# -.net
KiCad netlist of a schematic drawn in EasyEDA Pro
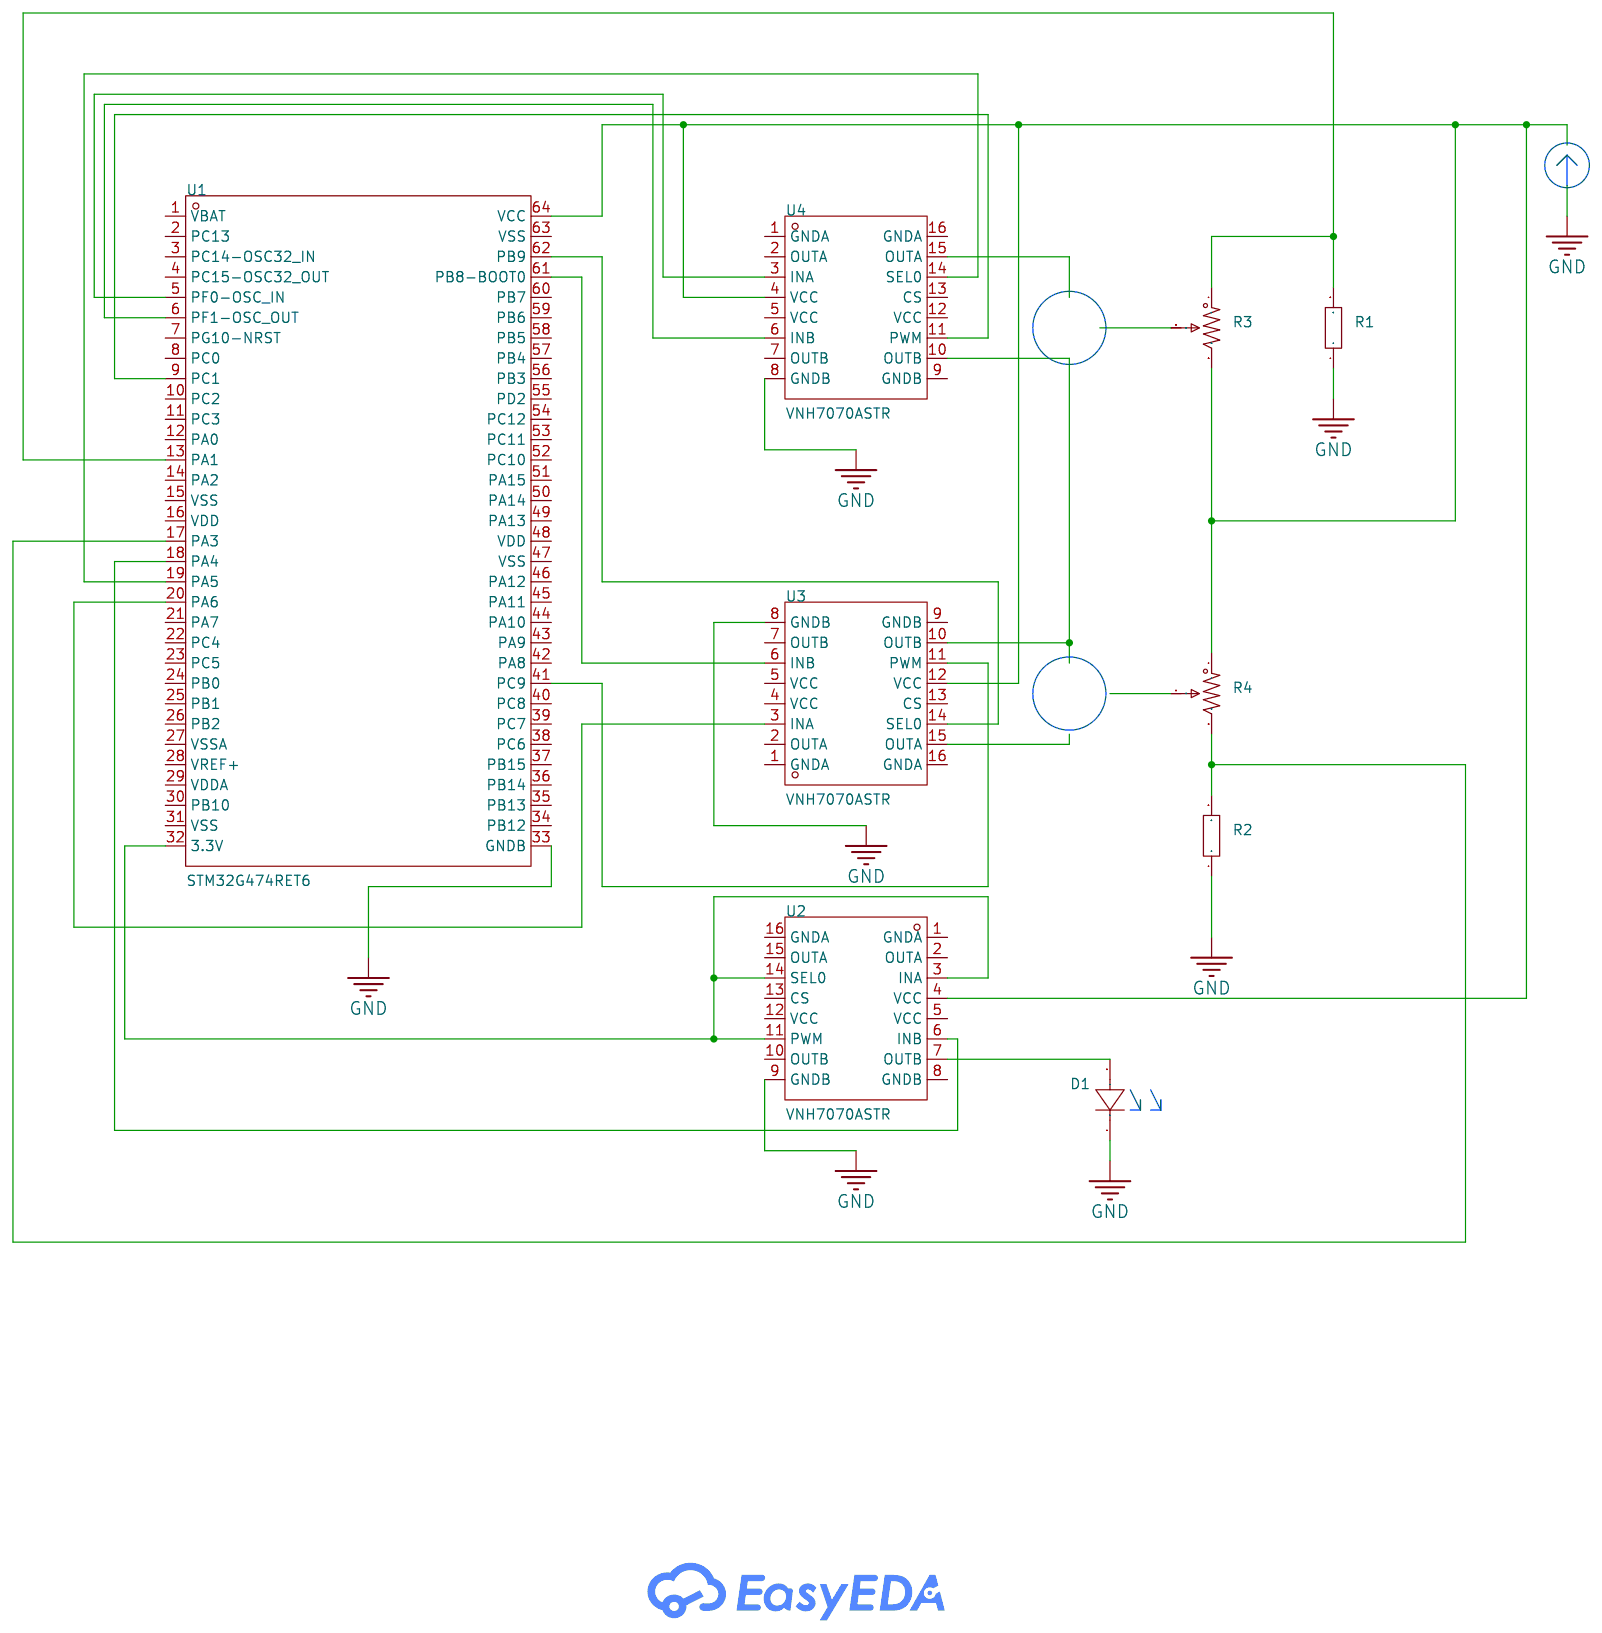
[diagram p0: schematic sheet]

(export (version "E")
  (design (tool "Eeschema 10.0.6"))
  (components
    (comp (ref "D1")
      (value "~")
      (footprint "easyedapro:SMA_L4.4-W2.8-LS5.4-RD")
      (libsource (lib "easyedapro") (part "D_1N4007"))
    )
    (comp (ref "R1")
      (value "10mΩ")
      (footprint "easyedapro:R1206")
      (fields (field (name "Manufacturer Part") "FMF06FTHR010-LH") (field (name "Manufacturer") "PSA(信昌电陶)"))
      (libsource (lib "easyedapro") (part "FMF06FTHR010-LHL"))
    )
    (comp (ref "R2")
      (value "10mΩ")
      (footprint "easyedapro:R1206")
      (fields (field (name "Manufacturer Part") "FMF06FTHR010-LH") (field (name "Manufacturer") "PSA(信昌电陶)"))
      (libsource (lib "easyedapro") (part "FMF06FTHR010-LHL"))
    )
    (comp (ref "R3")
      (value "10kΩ")
      (footprint "easyedapro:RES-ADJ-TH_3362P")
      (description "Resistance: Tolerance:±10% Tolerance:±10%")
      (fields (field (name "Manufacturer Part") "3362P-1-103") (field (name "Manufacturer") "BOCHEN(博晨)"))
      (libsource (lib "easyedapro") (part "3362P-1-103_C118956"))
    )
    (comp (ref "R4")
      (value "10kΩ")
      (footprint "easyedapro:RES-ADJ-TH_3362P")
      (description "Resistance: Tolerance:±10% Tolerance:±10%")
      (fields (field (name "Manufacturer Part") "3362P-1-103") (field (name "Manufacturer") "BOCHEN(博晨)"))
      (libsource (lib "easyedapro") (part "3362P-1-103_C118956"))
    )
    (comp (ref "U1")
      (value "STM32G474RET6")
      (footprint "easyedapro:LQFP-64_L10.0-W10.0-P0.50-LS12.0-BL")
      (fields (field (name "Manufacturer") "ST(意法半导体)"))
      (libsource (lib "easyedapro") (part "STM32G474RET6"))
    )
    (comp (ref "U2")
      (value "VNH7070ASTR")
      (footprint "easyedapro:SOIC-16_L9.9-W3.9-P1.27-LS6.0-BL")
      (fields (field (name "Manufacturer") "ST(意法半导体)"))
      (libsource (lib "easyedapro") (part "VNH7070ASTR"))
    )
    (comp (ref "U3")
      (value "VNH7070ASTR")
      (footprint "easyedapro:SOIC-16_L9.9-W3.9-P1.27-LS6.0-BL")
      (fields (field (name "Manufacturer") "ST(意法半导体)"))
      (libsource (lib "easyedapro") (part "VNH7070ASTR"))
    )
    (comp (ref "U4")
      (value "VNH7070ASTR")
      (footprint "easyedapro:SOIC-16_L9.9-W3.9-P1.27-LS6.0-BL")
      (fields (field (name "Manufacturer") "ST(意法半导体)"))
      (libsource (lib "easyedapro") (part "VNH7070ASTR"))
    )
  )
  (nets
    (net (code "1") (name "GND") (class "Default")
      (node (ref "D1") (pin "1") (pinfunction "K_1") (pintype "input"))
      (node (ref "R1") (pin "1") (pinfunction "1_1") (pintype "input"))
      (node (ref "R2") (pin "1") (pinfunction "1_1") (pintype "input"))
      (node (ref "U1") (pin "33") (pinfunction "GNDB_33") (pintype "unspecified"))
      (node (ref "U2") (pin "9") (pinfunction "GNDB_9") (pintype "unspecified"))
      (node (ref "U3") (pin "8") (pinfunction "GNDB_8") (pintype "unspecified"))
      (node (ref "U4") (pin "8") (pinfunction "GNDB_8") (pintype "unspecified"))
    )
    (net (code "2") (name "Net-(D1-A)") (class "Default")
      (node (ref "D1") (pin "2") (pinfunction "A_2") (pintype "input"))
      (node (ref "U2") (pin "7") (pinfunction "OUTB_7") (pintype "unspecified"))
    )
    (net (code "3") (name "Net-(U1-3.3V)") (class "Default")
      (node (ref "U1") (pin "32") (pinfunction "3.3V_32") (pintype "unspecified"))
      (node (ref "U2") (pin "11") (pinfunction "PWM_11") (pintype "unspecified"))
      (node (ref "U2") (pin "14") (pinfunction "SEL0_14") (pintype "unspecified"))
      (node (ref "U2") (pin "3") (pinfunction "INA_3") (pintype "unspecified"))
    )
    (net (code "4") (name "Net-(U1-PA1)") (class "Default")
      (node (ref "R1") (pin "2") (pinfunction "2_2") (pintype "input"))
      (node (ref "R3") (pin "1") (pinfunction "1_1") (pintype "unspecified"))
      (node (ref "U1") (pin "13") (pinfunction "PA1_13") (pintype "unspecified"))
    )
    (net (code "5") (name "Net-(U1-PA3)") (class "Default")
      (node (ref "R2") (pin "2") (pinfunction "2_2") (pintype "input"))
      (node (ref "R4") (pin "3") (pinfunction "3_3") (pintype "unspecified"))
      (node (ref "U1") (pin "17") (pinfunction "PA3_17") (pintype "unspecified"))
    )
    (net (code "6") (name "Net-(U1-PA4)") (class "Default")
      (node (ref "U1") (pin "18") (pinfunction "PA4_18") (pintype "unspecified"))
      (node (ref "U2") (pin "6") (pinfunction "INB_6") (pintype "unspecified"))
    )
    (net (code "7") (name "Net-(U1-PA5)") (class "Default")
      (node (ref "U1") (pin "19") (pinfunction "PA5_19") (pintype "unspecified"))
      (node (ref "U4") (pin "14") (pinfunction "SEL0_14") (pintype "unspecified"))
    )
    (net (code "8") (name "Net-(U1-PA6)") (class "Default")
      (node (ref "U1") (pin "20") (pinfunction "PA6_20") (pintype "unspecified"))
      (node (ref "U3") (pin "3") (pinfunction "INA_3") (pintype "unspecified"))
    )
    (net (code "9") (name "Net-(U1-PB8-BOOT0)") (class "Default")
      (node (ref "U1") (pin "61") (pinfunction "PB8-BOOT0_61") (pintype "unspecified"))
      (node (ref "U3") (pin "6") (pinfunction "INB_6") (pintype "unspecified"))
    )
    (net (code "10") (name "Net-(U1-PB9)") (class "Default")
      (node (ref "U1") (pin "62") (pinfunction "PB9_62") (pintype "unspecified"))
      (node (ref "U3") (pin "14") (pinfunction "SEL0_14") (pintype "unspecified"))
    )
    (net (code "11") (name "Net-(U1-PC1)") (class "Default")
      (node (ref "U1") (pin "9") (pinfunction "PC1_9") (pintype "unspecified"))
      (node (ref "U4") (pin "11") (pinfunction "PWM_11") (pintype "unspecified"))
    )
    (net (code "12") (name "Net-(U1-PC9)") (class "Default")
      (node (ref "U1") (pin "41") (pinfunction "PC9_41") (pintype "unspecified"))
      (node (ref "U3") (pin "11") (pinfunction "PWM_11") (pintype "unspecified"))
    )
    (net (code "13") (name "Net-(U1-PF0-OSC_IN)") (class "Default")
      (node (ref "U1") (pin "5") (pinfunction "PF0-OSC_IN_5") (pintype "unspecified"))
      (node (ref "U4") (pin "3") (pinfunction "INA_3") (pintype "unspecified"))
    )
    (net (code "14") (name "Net-(U1-PF1-OSC_OUT)") (class "Default")
      (node (ref "U1") (pin "6") (pinfunction "PF1-OSC_OUT_6") (pintype "unspecified"))
      (node (ref "U4") (pin "6") (pinfunction "INB_6") (pintype "unspecified"))
    )
    (net (code "15") (name "Net-(U1-VCC)") (class "Default")
      (node (ref "R3") (pin "3") (pinfunction "3_3") (pintype "unspecified"))
      (node (ref "R4") (pin "1") (pinfunction "1_1") (pintype "unspecified"))
      (node (ref "U1") (pin "64") (pinfunction "VCC_64") (pintype "unspecified"))
      (node (ref "U2") (pin "4") (pinfunction "VCC_4") (pintype "unspecified"))
      (node (ref "U3") (pin "12") (pinfunction "VCC_12") (pintype "unspecified"))
      (node (ref "U4") (pin "4") (pinfunction "VCC_4") (pintype "unspecified"))
    )
    (net (code "16") (name "Net-(U3-OUTB-Pad10)") (class "Default")
      (node (ref "U3") (pin "10") (pinfunction "OUTB_10") (pintype "unspecified"))
      (node (ref "U4") (pin "10") (pinfunction "OUTB_10") (pintype "unspecified"))
    )
    (net (code "17") (name "unconnected-(R3-Pad2)") (class "Default")
      (node (ref "R3") (pin "2") (pinfunction "2_2") (pintype "unspecified"))
    )
    (net (code "18") (name "unconnected-(R4-Pad2)") (class "Default")
      (node (ref "R4") (pin "2") (pinfunction "2_2") (pintype "unspecified"))
    )
    (net (code "19") (name "unconnected-(U1-PA0-Pad12)") (class "Default")
      (node (ref "U1") (pin "12") (pinfunction "PA0_12") (pintype "unspecified"))
    )
    (net (code "20") (name "unconnected-(U1-PA2-Pad14)") (class "Default")
      (node (ref "U1") (pin "14") (pinfunction "PA2_14") (pintype "unspecified"))
    )
    (net (code "21") (name "unconnected-(U1-PA7-Pad21)") (class "Default")
      (node (ref "U1") (pin "21") (pinfunction "PA7_21") (pintype "unspecified"))
    )
    (net (code "22") (name "unconnected-(U1-PA8-Pad42)") (class "Default")
      (node (ref "U1") (pin "42") (pinfunction "PA8_42") (pintype "unspecified"))
    )
    (net (code "23") (name "unconnected-(U1-PA9-Pad43)") (class "Default")
      (node (ref "U1") (pin "43") (pinfunction "PA9_43") (pintype "unspecified"))
    )
    (net (code "24") (name "unconnected-(U1-PA10-Pad44)") (class "Default")
      (node (ref "U1") (pin "44") (pinfunction "PA10_44") (pintype "unspecified"))
    )
    (net (code "25") (name "unconnected-(U1-PA11-Pad45)") (class "Default")
      (node (ref "U1") (pin "45") (pinfunction "PA11_45") (pintype "unspecified"))
    )
    (net (code "26") (name "unconnected-(U1-PA12-Pad46)") (class "Default")
      (node (ref "U1") (pin "46") (pinfunction "PA12_46") (pintype "unspecified"))
    )
    (net (code "27") (name "unconnected-(U1-PA13-Pad49)") (class "Default")
      (node (ref "U1") (pin "49") (pinfunction "PA13_49") (pintype "unspecified"))
    )
    (net (code "28") (name "unconnected-(U1-PA14-Pad50)") (class "Default")
      (node (ref "U1") (pin "50") (pinfunction "PA14_50") (pintype "unspecified"))
    )
    (net (code "29") (name "unconnected-(U1-PA15-Pad51)") (class "Default")
      (node (ref "U1") (pin "51") (pinfunction "PA15_51") (pintype "unspecified"))
    )
    (net (code "30") (name "unconnected-(U1-PB0-Pad24)") (class "Default")
      (node (ref "U1") (pin "24") (pinfunction "PB0_24") (pintype "unspecified"))
    )
    (net (code "31") (name "unconnected-(U1-PB1-Pad25)") (class "Default")
      (node (ref "U1") (pin "25") (pinfunction "PB1_25") (pintype "unspecified"))
    )
    (net (code "32") (name "unconnected-(U1-PB2-Pad26)") (class "Default")
      (node (ref "U1") (pin "26") (pinfunction "PB2_26") (pintype "unspecified"))
    )
    (net (code "33") (name "unconnected-(U1-PB3-Pad56)") (class "Default")
      (node (ref "U1") (pin "56") (pinfunction "PB3_56") (pintype "unspecified"))
    )
    (net (code "34") (name "unconnected-(U1-PB4-Pad57)") (class "Default")
      (node (ref "U1") (pin "57") (pinfunction "PB4_57") (pintype "unspecified"))
    )
    (net (code "35") (name "unconnected-(U1-PB5-Pad58)") (class "Default")
      (node (ref "U1") (pin "58") (pinfunction "PB5_58") (pintype "unspecified"))
    )
    (net (code "36") (name "unconnected-(U1-PB6-Pad59)") (class "Default")
      (node (ref "U1") (pin "59") (pinfunction "PB6_59") (pintype "unspecified"))
    )
    (net (code "37") (name "unconnected-(U1-PB7-Pad60)") (class "Default")
      (node (ref "U1") (pin "60") (pinfunction "PB7_60") (pintype "unspecified"))
    )
    (net (code "38") (name "unconnected-(U1-PB10-Pad30)") (class "Default")
      (node (ref "U1") (pin "30") (pinfunction "PB10_30") (pintype "unspecified"))
    )
    (net (code "39") (name "unconnected-(U1-PB12-Pad34)") (class "Default")
      (node (ref "U1") (pin "34") (pinfunction "PB12_34") (pintype "unspecified"))
    )
    (net (code "40") (name "unconnected-(U1-PB13-Pad35)") (class "Default")
      (node (ref "U1") (pin "35") (pinfunction "PB13_35") (pintype "unspecified"))
    )
    (net (code "41") (name "unconnected-(U1-PB14-Pad36)") (class "Default")
      (node (ref "U1") (pin "36") (pinfunction "PB14_36") (pintype "unspecified"))
    )
    (net (code "42") (name "unconnected-(U1-PB15-Pad37)") (class "Default")
      (node (ref "U1") (pin "37") (pinfunction "PB15_37") (pintype "unspecified"))
    )
    (net (code "43") (name "unconnected-(U1-PC0-Pad8)") (class "Default")
      (node (ref "U1") (pin "8") (pinfunction "PC0_8") (pintype "unspecified"))
    )
    (net (code "44") (name "unconnected-(U1-PC2-Pad10)") (class "Default")
      (node (ref "U1") (pin "10") (pinfunction "PC2_10") (pintype "unspecified"))
    )
    (net (code "45") (name "unconnected-(U1-PC3-Pad11)") (class "Default")
      (node (ref "U1") (pin "11") (pinfunction "PC3_11") (pintype "unspecified"))
    )
    (net (code "46") (name "unconnected-(U1-PC4-Pad22)") (class "Default")
      (node (ref "U1") (pin "22") (pinfunction "PC4_22") (pintype "unspecified"))
    )
    (net (code "47") (name "unconnected-(U1-PC5-Pad23)") (class "Default")
      (node (ref "U1") (pin "23") (pinfunction "PC5_23") (pintype "unspecified"))
    )
    (net (code "48") (name "unconnected-(U1-PC6-Pad38)") (class "Default")
      (node (ref "U1") (pin "38") (pinfunction "PC6_38") (pintype "unspecified"))
    )
    (net (code "49") (name "unconnected-(U1-PC7-Pad39)") (class "Default")
      (node (ref "U1") (pin "39") (pinfunction "PC7_39") (pintype "unspecified"))
    )
    (net (code "50") (name "unconnected-(U1-PC8-Pad40)") (class "Default")
      (node (ref "U1") (pin "40") (pinfunction "PC8_40") (pintype "unspecified"))
    )
    (net (code "51") (name "unconnected-(U1-PC10-Pad52)") (class "Default")
      (node (ref "U1") (pin "52") (pinfunction "PC10_52") (pintype "unspecified"))
    )
    (net (code "52") (name "unconnected-(U1-PC11-Pad53)") (class "Default")
      (node (ref "U1") (pin "53") (pinfunction "PC11_53") (pintype "unspecified"))
    )
    (net (code "53") (name "unconnected-(U1-PC12-Pad54)") (class "Default")
      (node (ref "U1") (pin "54") (pinfunction "PC12_54") (pintype "unspecified"))
    )
    (net (code "54") (name "unconnected-(U1-PC13-Pad2)") (class "Default")
      (node (ref "U1") (pin "2") (pinfunction "PC13_2") (pintype "unspecified"))
    )
    (net (code "55") (name "unconnected-(U1-PC14-OSC32_IN-Pad3)") (class "Default")
      (node (ref "U1") (pin "3") (pinfunction "PC14-OSC32_IN_3") (pintype "unspecified"))
    )
    (net (code "56") (name "unconnected-(U1-PC15-OSC32_OUT-Pad4)") (class "Default")
      (node (ref "U1") (pin "4") (pinfunction "PC15-OSC32_OUT_4") (pintype "unspecified"))
    )
    (net (code "57") (name "unconnected-(U1-PD2-Pad55)") (class "Default")
      (node (ref "U1") (pin "55") (pinfunction "PD2_55") (pintype "unspecified"))
    )
    (net (code "58") (name "unconnected-(U1-PG10-NRST-Pad7)") (class "Default")
      (node (ref "U1") (pin "7") (pinfunction "PG10-NRST_7") (pintype "unspecified"))
    )
    (net (code "59") (name "unconnected-(U1-VBAT-Pad1)") (class "Default")
      (node (ref "U1") (pin "1") (pinfunction "VBAT_1") (pintype "unspecified"))
    )
    (net (code "60") (name "unconnected-(U1-VDD-Pad16)") (class "Default")
      (node (ref "U1") (pin "16") (pinfunction "VDD_16") (pintype "unspecified"))
    )
    (net (code "61") (name "unconnected-(U1-VDD-Pad48)") (class "Default")
      (node (ref "U1") (pin "48") (pinfunction "VDD_48") (pintype "unspecified"))
    )
    (net (code "62") (name "unconnected-(U1-VDDA-Pad29)") (class "Default")
      (node (ref "U1") (pin "29") (pinfunction "VDDA_29") (pintype "unspecified"))
    )
    (net (code "63") (name "unconnected-(U1-VREF+-Pad28)") (class "Default")
      (node (ref "U1") (pin "28") (pinfunction "VREF+_28") (pintype "unspecified"))
    )
    (net (code "64") (name "unconnected-(U1-VSS-Pad15)") (class "Default")
      (node (ref "U1") (pin "15") (pinfunction "VSS_15") (pintype "unspecified"))
    )
    (net (code "65") (name "unconnected-(U1-VSS-Pad31)") (class "Default")
      (node (ref "U1") (pin "31") (pinfunction "VSS_31") (pintype "unspecified"))
    )
    (net (code "66") (name "unconnected-(U1-VSS-Pad47)") (class "Default")
      (node (ref "U1") (pin "47") (pinfunction "VSS_47") (pintype "unspecified"))
    )
    (net (code "67") (name "unconnected-(U1-VSS-Pad63)") (class "Default")
      (node (ref "U1") (pin "63") (pinfunction "VSS_63") (pintype "unspecified"))
    )
    (net (code "68") (name "unconnected-(U1-VSSA-Pad27)") (class "Default")
      (node (ref "U1") (pin "27") (pinfunction "VSSA_27") (pintype "unspecified"))
    )
    (net (code "69") (name "unconnected-(U2-CS-Pad13)") (class "Default")
      (node (ref "U2") (pin "13") (pinfunction "CS_13") (pintype "unspecified"))
    )
    (net (code "70") (name "unconnected-(U2-GNDA-Pad1)") (class "Default")
      (node (ref "U2") (pin "1") (pinfunction "GNDA_1") (pintype "unspecified"))
    )
    (net (code "71") (name "unconnected-(U2-GNDA-Pad16)") (class "Default")
      (node (ref "U2") (pin "16") (pinfunction "GNDA_16") (pintype "unspecified"))
    )
    (net (code "72") (name "unconnected-(U2-GNDB-Pad8)") (class "Default")
      (node (ref "U2") (pin "8") (pinfunction "GNDB_8") (pintype "unspecified"))
    )
    (net (code "73") (name "unconnected-(U2-OUTA-Pad2)") (class "Default")
      (node (ref "U2") (pin "2") (pinfunction "OUTA_2") (pintype "unspecified"))
    )
    (net (code "74") (name "unconnected-(U2-OUTA-Pad15)") (class "Default")
      (node (ref "U2") (pin "15") (pinfunction "OUTA_15") (pintype "unspecified"))
    )
    (net (code "75") (name "unconnected-(U2-OUTB-Pad10)") (class "Default")
      (node (ref "U2") (pin "10") (pinfunction "OUTB_10") (pintype "unspecified"))
    )
    (net (code "76") (name "unconnected-(U2-VCC-Pad5)") (class "Default")
      (node (ref "U2") (pin "5") (pinfunction "VCC_5") (pintype "unspecified"))
    )
    (net (code "77") (name "unconnected-(U2-VCC-Pad12)") (class "Default")
      (node (ref "U2") (pin "12") (pinfunction "VCC_12") (pintype "unspecified"))
    )
    (net (code "78") (name "unconnected-(U3-CS-Pad13)") (class "Default")
      (node (ref "U3") (pin "13") (pinfunction "CS_13") (pintype "unspecified"))
    )
    (net (code "79") (name "unconnected-(U3-GNDA-Pad1)") (class "Default")
      (node (ref "U3") (pin "1") (pinfunction "GNDA_1") (pintype "unspecified"))
    )
    (net (code "80") (name "unconnected-(U3-GNDA-Pad16)") (class "Default")
      (node (ref "U3") (pin "16") (pinfunction "GNDA_16") (pintype "unspecified"))
    )
    (net (code "81") (name "unconnected-(U3-GNDB-Pad9)") (class "Default")
      (node (ref "U3") (pin "9") (pinfunction "GNDB_9") (pintype "unspecified"))
    )
    (net (code "82") (name "unconnected-(U3-OUTA-Pad2)") (class "Default")
      (node (ref "U3") (pin "2") (pinfunction "OUTA_2") (pintype "unspecified"))
    )
    (net (code "83") (name "unconnected-(U3-OUTA-Pad15)") (class "Default")
      (node (ref "U3") (pin "15") (pinfunction "OUTA_15") (pintype "unspecified"))
    )
    (net (code "84") (name "unconnected-(U3-OUTB-Pad7)") (class "Default")
      (node (ref "U3") (pin "7") (pinfunction "OUTB_7") (pintype "unspecified"))
    )
    (net (code "85") (name "unconnected-(U3-VCC-Pad4)") (class "Default")
      (node (ref "U3") (pin "4") (pinfunction "VCC_4") (pintype "unspecified"))
    )
    (net (code "86") (name "unconnected-(U3-VCC-Pad5)") (class "Default")
      (node (ref "U3") (pin "5") (pinfunction "VCC_5") (pintype "unspecified"))
    )
    (net (code "87") (name "unconnected-(U4-CS-Pad13)") (class "Default")
      (node (ref "U4") (pin "13") (pinfunction "CS_13") (pintype "unspecified"))
    )
    (net (code "88") (name "unconnected-(U4-GNDA-Pad1)") (class "Default")
      (node (ref "U4") (pin "1") (pinfunction "GNDA_1") (pintype "unspecified"))
    )
    (net (code "89") (name "unconnected-(U4-GNDA-Pad16)") (class "Default")
      (node (ref "U4") (pin "16") (pinfunction "GNDA_16") (pintype "unspecified"))
    )
    (net (code "90") (name "unconnected-(U4-GNDB-Pad9)") (class "Default")
      (node (ref "U4") (pin "9") (pinfunction "GNDB_9") (pintype "unspecified"))
    )
    (net (code "91") (name "unconnected-(U4-OUTA-Pad2)") (class "Default")
      (node (ref "U4") (pin "2") (pinfunction "OUTA_2") (pintype "unspecified"))
    )
    (net (code "92") (name "unconnected-(U4-OUTA-Pad15)") (class "Default")
      (node (ref "U4") (pin "15") (pinfunction "OUTA_15") (pintype "unspecified"))
    )
    (net (code "93") (name "unconnected-(U4-OUTB-Pad7)") (class "Default")
      (node (ref "U4") (pin "7") (pinfunction "OUTB_7") (pintype "unspecified"))
    )
    (net (code "94") (name "unconnected-(U4-VCC-Pad5)") (class "Default")
      (node (ref "U4") (pin "5") (pinfunction "VCC_5") (pintype "unspecified"))
    )
    (net (code "95") (name "unconnected-(U4-VCC-Pad12)") (class "Default")
      (node (ref "U4") (pin "12") (pinfunction "VCC_12") (pintype "unspecified"))
    )
  )
)
